# switching_noise_board.net
KiCad netlist of a schematic drawn in Altium Designer
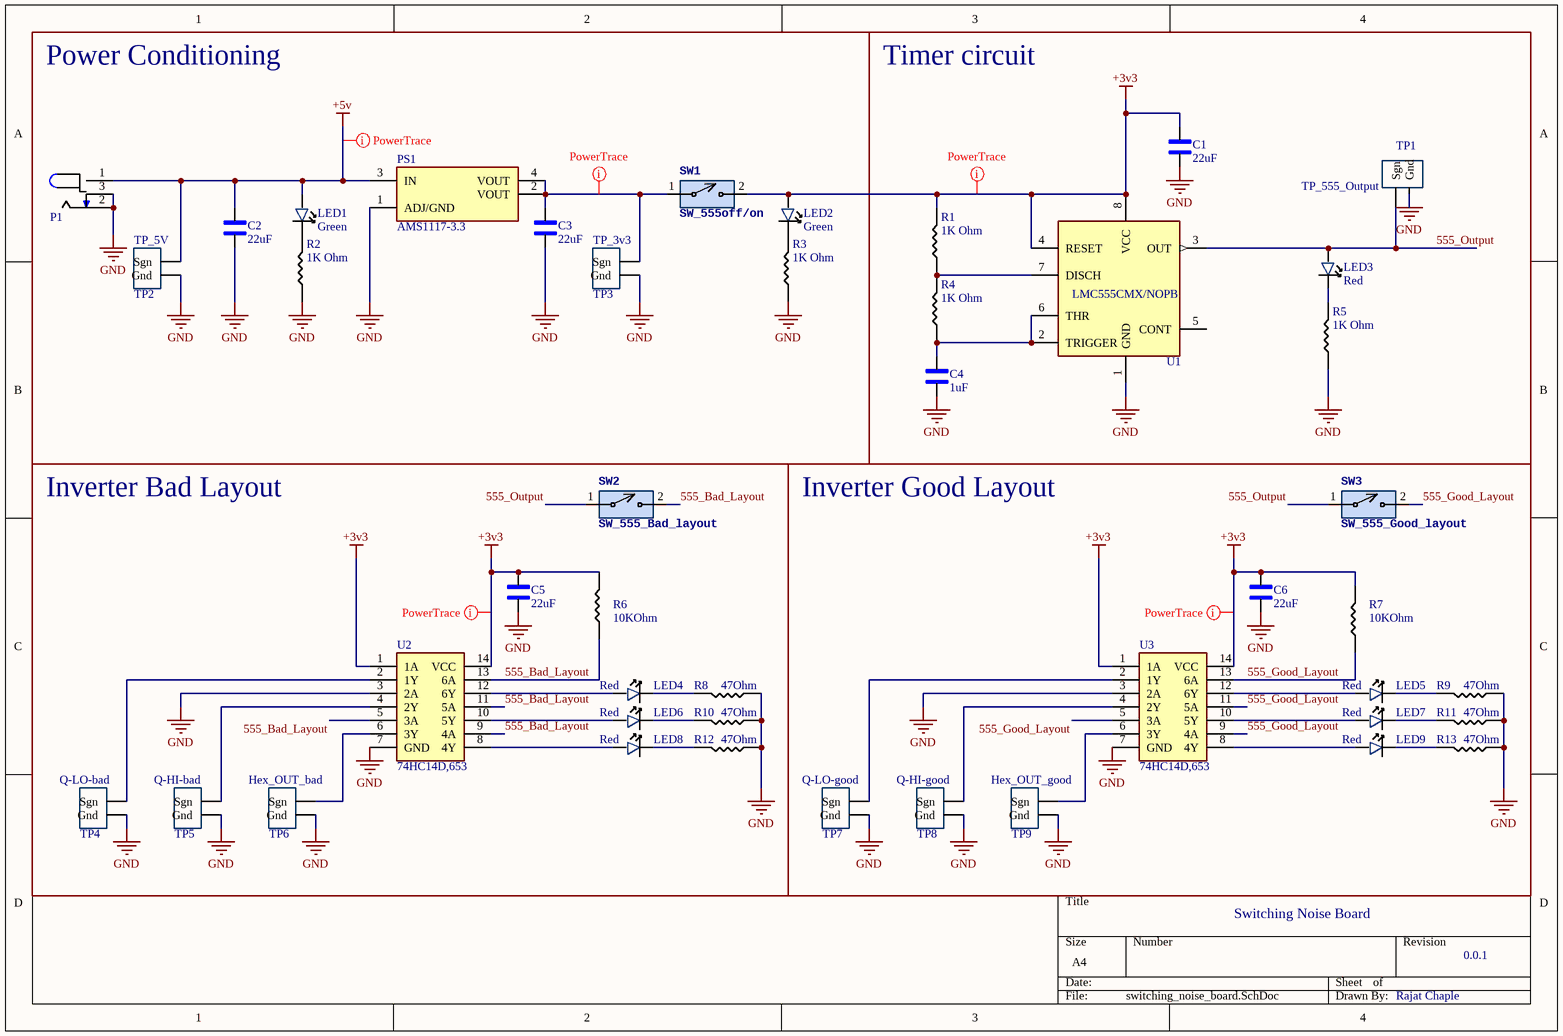
[diagram p0: switching_noise_board.SchDoc]

(export (version "E")
  (design (tool "Eeschema 10.0.6"))
  (components
    (comp (ref "C1")
      (value "22uF")
      (footprint "0805_Passive_Capaciitor")
      (description "MULTILAYER CERAMIC CAPACITORS MLCC - SMD/SMT 22UF 25V 0805 ROHS")
      (fields (field (name "MFR PART #") "CL21A226MAQNNNE") (field (name "LCSC PART#") "C45783"))
      (libsource (lib "ECEN5730Lib_JLC_2021_08") (part "C_22uF_0805"))
    )
    (comp (ref "C2")
      (value "22uF")
      (footprint "0805_Passive_Capaciitor")
      (description "MULTILAYER CERAMIC CAPACITORS MLCC - SMD/SMT 22UF 25V 0805 ROHS")
      (fields (field (name "MFR PART #") "CL21A226MAQNNNE") (field (name "LCSC PART#") "C45783"))
      (libsource (lib "ECEN5730Lib_JLC_2021_08") (part "C_22uF_0805"))
    )
    (comp (ref "C3")
      (value "22uF")
      (footprint "0805_Passive_Capaciitor")
      (description "MULTILAYER CERAMIC CAPACITORS MLCC - SMD/SMT 22UF 25V 0805 ROHS")
      (fields (field (name "MFR PART #") "CL21A226MAQNNNE") (field (name "LCSC PART#") "C45783"))
      (libsource (lib "ECEN5730Lib_JLC_2021_08") (part "C_22uF_0805"))
    )
    (comp (ref "C4")
      (value "1uF")
      (footprint "0402_Passive_Capacitor")
      (description "MULTILAYER CERAMIC CAPACITORS MLCC - SMD/SMT 1UF 25V 0402 ROHS")
      (fields (field (name "MFR PART #") "CL05A105KA5NQNC") (field (name "LCSC PART#") "C52923"))
      (libsource (lib "ECEN5730Lib_JLC_2021_08") (part "C_1uF_0402"))
    )
    (comp (ref "C5")
      (value "22uF")
      (footprint "0805_Passive_Capaciitor")
      (description "MULTILAYER CERAMIC CAPACITORS MLCC - SMD/SMT 22UF 25V 0805 ROHS")
      (fields (field (name "MFR PART #") "CL21A226MAQNNNE") (field (name "LCSC PART#") "C45783"))
      (libsource (lib "ECEN5730Lib_JLC_2021_08") (part "C_22uF_0805"))
    )
    (comp (ref "C6")
      (value "22uF")
      (footprint "0805_Passive_Capaciitor")
      (description "MULTILAYER CERAMIC CAPACITORS MLCC - SMD/SMT 22UF 25V 0805 ROHS")
      (fields (field (name "MFR PART #") "CL21A226MAQNNNE") (field (name "LCSC PART#") "C45783"))
      (libsource (lib "ECEN5730Lib_JLC_2021_08") (part "C_22uF_0805"))
    )
    (comp (ref "LED1")
      (value "Green")
      (footprint "LED_0603")
      (description "LIGHT EMITTING DIODES (LED) GREEN 520~535NM 112~258MCD@20MA TOP VIEW 0603 ROHS")
      (fields (field (name "MFR PART #") "19-217/GHC-YR1S2/3T") (field (name "LCSC PART#") "C72043"))
      (libsource (lib "ECEN5730Lib_JLC_2021_08") (part "LED_GREEN_0603"))
    )
    (comp (ref "LED2")
      (value "Green")
      (footprint "LED_0603")
      (description "LIGHT EMITTING DIODES (LED) GREEN 520~535NM 112~258MCD@20MA TOP VIEW 0603 ROHS")
      (fields (field (name "MFR PART #") "19-217/GHC-YR1S2/3T") (field (name "LCSC PART#") "C72043"))
      (libsource (lib "ECEN5730Lib_JLC_2021_08") (part "LED_GREEN_0603"))
    )
    (comp (ref "LED3")
      (value "Red")
      (footprint "LED_0603")
      (description "LIGHT EMITTING DIODES (LED) RED 520~625NM 90~100MCD@20MA TOP VIEW 0603 ROHS")
      (fields (field (name "MFR PART #") "KT-0603R") (field (name "LCSC PART#") "C2286"))
      (libsource (lib "ECEN5730Lib_JLC_2021_08") (part "LED_RED_0603"))
    )
    (comp (ref "LED4")
      (value "Red")
      (footprint "LED_0603")
      (description "LIGHT EMITTING DIODES (LED) RED 520~625NM 90~100MCD@20MA TOP VIEW 0603 ROHS")
      (fields (field (name "MFR PART #") "KT-0603R") (field (name "LCSC PART#") "C2286"))
      (libsource (lib "ECEN5730Lib_JLC_2021_08") (part "LED_RED_0603"))
    )
    (comp (ref "LED5")
      (value "Red")
      (footprint "LED_0603")
      (description "LIGHT EMITTING DIODES (LED) RED 520~625NM 90~100MCD@20MA TOP VIEW 0603 ROHS")
      (fields (field (name "MFR PART #") "KT-0603R") (field (name "LCSC PART#") "C2286"))
      (libsource (lib "ECEN5730Lib_JLC_2021_08") (part "LED_RED_0603"))
    )
    (comp (ref "LED6")
      (value "Red")
      (footprint "LED_0603")
      (description "LIGHT EMITTING DIODES (LED) RED 520~625NM 90~100MCD@20MA TOP VIEW 0603 ROHS")
      (fields (field (name "MFR PART #") "KT-0603R") (field (name "LCSC PART#") "C2286"))
      (libsource (lib "ECEN5730Lib_JLC_2021_08") (part "LED_RED_0603"))
    )
    (comp (ref "LED7")
      (value "Red")
      (footprint "LED_0603")
      (description "LIGHT EMITTING DIODES (LED) RED 520~625NM 90~100MCD@20MA TOP VIEW 0603 ROHS")
      (fields (field (name "MFR PART #") "KT-0603R") (field (name "LCSC PART#") "C2286"))
      (libsource (lib "ECEN5730Lib_JLC_2021_08") (part "LED_RED_0603"))
    )
    (comp (ref "LED8")
      (value "Red")
      (footprint "LED_0603")
      (description "LIGHT EMITTING DIODES (LED) RED 520~625NM 90~100MCD@20MA TOP VIEW 0603 ROHS")
      (fields (field (name "MFR PART #") "KT-0603R") (field (name "LCSC PART#") "C2286"))
      (libsource (lib "ECEN5730Lib_JLC_2021_08") (part "LED_RED_0603"))
    )
    (comp (ref "LED9")
      (value "Red")
      (footprint "LED_0603")
      (description "LIGHT EMITTING DIODES (LED) RED 520~625NM 90~100MCD@20MA TOP VIEW 0603 ROHS")
      (fields (field (name "MFR PART #") "KT-0603R") (field (name "LCSC PART#") "C2286"))
      (libsource (lib "ECEN5730Lib_JLC_2021_08") (part "LED_RED_0603"))
    )
    (comp (ref "P1")
      (value "Power Jack")
      (footprint "Power_Jack")
      (description "Power Barrel Connector Jack 2.10mm ID (0.083\"), 5.50mm OD (0.217\") Through Hole, Right Angle")
      (fields (field (name "DIGIKEY PART") "CP-102A-ND") (field (name "LCSC PART#") "C136744"))
      (libsource (lib "ECEN5730Lib_JLC_2021_08") (part "P_Power Jack"))
    )
    (comp (ref "PS1")
      (value "AMS1117-3.3")
      (footprint "LDO")
      (description "LOW DROPOUT REGULATORS(LDO) POSITIVE FIXED 1.3V @ 800MA 15V 3.3V 1A SOT-223 ROHS")
      (fields (field (name "LCSC PART#") "C6186"))
      (libsource (lib "ECEN5730Lib_JLC_2021_08") (part "PS_AMS_LDO_3v3"))
    )
    (comp (ref "R1")
      (value "1K Ohm")
      (footprint "0805_Passive_Resistor")
      (description "CHIP RESISTOR - SURFACE MOUNT 1KOHMS ±1% 1/8W 0805 ROHS")
      (fields (field (name "LCSC PART#") "C17513") (field (name "MFR PART #") "0805W8F1001T5E"))
      (libsource (lib "ECEN5730Lib_JLC_2021_08") (part "R_1K_0805"))
    )
    (comp (ref "R2")
      (value "1K Ohm")
      (footprint "0805_Passive_Resistor")
      (description "CHIP RESISTOR - SURFACE MOUNT 1KOHMS ±1% 1/8W 0805 ROHS")
      (fields (field (name "LCSC PART#") "C17513") (field (name "MFR PART #") "0805W8F1001T5E"))
      (libsource (lib "ECEN5730Lib_JLC_2021_08") (part "R_1K_0805"))
    )
    (comp (ref "R3")
      (value "1K Ohm")
      (footprint "0805_Passive_Resistor")
      (description "CHIP RESISTOR - SURFACE MOUNT 1KOHMS ±1% 1/8W 0805 ROHS")
      (fields (field (name "LCSC PART#") "C17513") (field (name "MFR PART #") "0805W8F1001T5E"))
      (libsource (lib "ECEN5730Lib_JLC_2021_08") (part "R_1K_0805"))
    )
    (comp (ref "R4")
      (value "1K Ohm")
      (footprint "0805_Passive_Resistor")
      (description "CHIP RESISTOR - SURFACE MOUNT 1KOHMS ±1% 1/8W 0805 ROHS")
      (fields (field (name "LCSC PART#") "C17513") (field (name "MFR PART #") "0805W8F1001T5E"))
      (libsource (lib "ECEN5730Lib_JLC_2021_08") (part "R_1K_0805"))
    )
    (comp (ref "R5")
      (value "1K Ohm")
      (footprint "0805_Passive_Resistor")
      (description "CHIP RESISTOR - SURFACE MOUNT 1KOHMS ±1% 1/8W 0805 ROHS")
      (fields (field (name "LCSC PART#") "C17513") (field (name "MFR PART #") "0805W8F1001T5E"))
      (libsource (lib "ECEN5730Lib_JLC_2021_08") (part "R_1K_0805"))
    )
    (comp (ref "R6")
      (value "10KOhm")
      (footprint "0402_Passive_Resistor")
      (description "CHIP RESISTOR - SURFACE MOUNT 10KOHMS ±1% 1/16W 0402 ROHS")
      (fields (field (name "MFR PART #") "0402WGF1002TCE") (field (name "LCSC PART#") "C25744"))
      (libsource (lib "ECEN5730Lib_JLC_2021_08") (part "R_10KOhm_0402"))
    )
    (comp (ref "R7")
      (value "10KOhm")
      (footprint "0402_Passive_Resistor")
      (description "CHIP RESISTOR - SURFACE MOUNT 10KOHMS ±1% 1/16W 0402 ROHS")
      (fields (field (name "MFR PART #") "0402WGF1002TCE") (field (name "LCSC PART#") "C25744"))
      (libsource (lib "ECEN5730Lib_JLC_2021_08") (part "R_10KOhm_0402"))
    )
    (comp (ref "R8")
      (value "47Ohm")
      (footprint "0402_Passive_Resistor")
      (description "CHIP RESISTOR - SURFACE MOUNT 47OHMS ±1% 1/16W 0402 ROHS")
      (fields (field (name "MFR PART #") "0402WGF470JTCE") (field (name "LCSC PART#") "C25118"))
      (libsource (lib "ECEN5730Lib_JLC_2021_08") (part "R_47Ohm_0402"))
    )
    (comp (ref "R9")
      (value "47Ohm")
      (footprint "0402_Passive_Resistor")
      (description "CHIP RESISTOR - SURFACE MOUNT 47OHMS ±1% 1/16W 0402 ROHS")
      (fields (field (name "MFR PART #") "0402WGF470JTCE") (field (name "LCSC PART#") "C25118"))
      (libsource (lib "ECEN5730Lib_JLC_2021_08") (part "R_47Ohm_0402"))
    )
    (comp (ref "R10")
      (value "47Ohm")
      (footprint "0402_Passive_Resistor")
      (description "CHIP RESISTOR - SURFACE MOUNT 47OHMS ±1% 1/16W 0402 ROHS")
      (fields (field (name "MFR PART #") "0402WGF470JTCE") (field (name "LCSC PART#") "C25118"))
      (libsource (lib "ECEN5730Lib_JLC_2021_08") (part "R_47Ohm_0402"))
    )
    (comp (ref "R11")
      (value "47Ohm")
      (footprint "0402_Passive_Resistor")
      (description "CHIP RESISTOR - SURFACE MOUNT 47OHMS ±1% 1/16W 0402 ROHS")
      (fields (field (name "MFR PART #") "0402WGF470JTCE") (field (name "LCSC PART#") "C25118"))
      (libsource (lib "ECEN5730Lib_JLC_2021_08") (part "R_47Ohm_0402"))
    )
    (comp (ref "R12")
      (value "47Ohm")
      (footprint "0402_Passive_Resistor")
      (description "CHIP RESISTOR - SURFACE MOUNT 47OHMS ±1% 1/16W 0402 ROHS")
      (fields (field (name "MFR PART #") "0402WGF470JTCE") (field (name "LCSC PART#") "C25118"))
      (libsource (lib "ECEN5730Lib_JLC_2021_08") (part "R_47Ohm_0402"))
    )
    (comp (ref "R13")
      (value "47Ohm")
      (footprint "0402_Passive_Resistor")
      (description "CHIP RESISTOR - SURFACE MOUNT 47OHMS ±1% 1/16W 0402 ROHS")
      (fields (field (name "MFR PART #") "0402WGF470JTCE") (field (name "LCSC PART#") "C25118"))
      (libsource (lib "ECEN5730Lib_JLC_2021_08") (part "R_47Ohm_0402"))
    )
    (comp (ref "SW1")
      (value "SW_555off/on")
      (footprint "2Pin-Header-Conn")
      (description "2Pin Header")
      (fields (field (name "LCSC PART#") "C124375"))
      (libsource (lib "ECEN5730Lib_JLC_2021_08") (part "SW_2Pin_100mil_Switch"))
    )
    (comp (ref "SW2")
      (value "SW_555_Bad_layout")
      (footprint "2Pin-Header-Conn")
      (description "2Pin Header")
      (fields (field (name "LCSC PART#") "C124375"))
      (libsource (lib "ECEN5730Lib_JLC_2021_08") (part "SW_2Pin_100mil_Switch"))
    )
    (comp (ref "SW3")
      (value "SW_555_Good_layout")
      (footprint "2Pin-Header-Conn")
      (description "2Pin Header")
      (fields (field (name "LCSC PART#") "C124375"))
      (libsource (lib "ECEN5730Lib_JLC_2021_08") (part "SW_2Pin_100mil_Switch"))
    )
    (comp (ref "TP1")
      (value "TP_555_Output")
      (footprint "TP10x_Probe")
      (description "Test Point 300 mil centers")
      (libsource (lib "") (part "TP_10x_Probe_1"))
    )
    (comp (ref "TP2")
      (value "TP_5V")
      (footprint "TP10x_Probe")
      (description "Test Point 300 mil centers")
      (libsource (lib "ECEN5730Lib_Manual_2021_08") (part "TP_10x_Probe"))
    )
    (comp (ref "TP3")
      (value "TP_3v3")
      (footprint "TP10x_Probe")
      (description "Test Point 300 mil centers")
      (libsource (lib "ECEN5730Lib_Manual_2021_08") (part "TP_10x_Probe"))
    )
    (comp (ref "TP4")
      (value "Q-LO-bad")
      (footprint "TP10x_Probe")
      (description "Test Point 300 mil centers")
      (libsource (lib "ECEN5730Lib_Manual_2021_08") (part "TP_10x_Probe"))
    )
    (comp (ref "TP5")
      (value "Q-HI-bad")
      (footprint "TP10x_Probe")
      (description "Test Point 300 mil centers")
      (libsource (lib "ECEN5730Lib_Manual_2021_08") (part "TP_10x_Probe"))
    )
    (comp (ref "TP6")
      (value "Hex_OUT_bad")
      (footprint "TP10x_Probe")
      (description "Test Point 300 mil centers")
      (libsource (lib "ECEN5730Lib_Manual_2021_08") (part "TP_10x_Probe"))
    )
    (comp (ref "TP7")
      (value "Q-LO-good")
      (footprint "TP10x_Probe")
      (description "Test Point 300 mil centers")
      (libsource (lib "ECEN5730Lib_Manual_2021_08") (part "TP_10x_Probe"))
    )
    (comp (ref "TP8")
      (value "Q-HI-good")
      (footprint "TP10x_Probe")
      (description "Test Point 300 mil centers")
      (libsource (lib "ECEN5730Lib_Manual_2021_08") (part "TP_10x_Probe"))
    )
    (comp (ref "TP9")
      (value "Hex_OUT_good")
      (footprint "TP10x_Probe")
      (description "Test Point 300 mil centers")
      (libsource (lib "ECEN5730Lib_Manual_2021_08") (part "TP_10x_Probe"))
    )
    (comp (ref "U1")
      (value "LMC555CMX/NOPB")
      (footprint "TS555IDTTR")
      (description "555 Type, Timer/Oscillator _Single_ IC 3MHz 8-SO")
      (fields (field (name "LCSC PART#") "C90760"))
      (libsource (lib "ECEN5730Lib_JLC_2021_08") (part "U_555_Fast"))
    )
    (comp (ref "U2")
      (value "74HC14D,653")
      (footprint "HEX_74AC14")
      (description "Inverter IC 6 Channel Schmitt Trigger 14-SOIC")
      (fields (field (name "LCSC PART#") "C5605"))
      (libsource (lib "ECEN5730Lib_JLC_2021_08") (part "U_7414_HC_Hex"))
    )
    (comp (ref "U3")
      (value "74HC14D,653")
      (footprint "HEX_74AC14")
      (description "Inverter IC 6 Channel Schmitt Trigger 14-SOIC")
      (fields (field (name "LCSC PART#") "C5605"))
      (libsource (lib "ECEN5730Lib_JLC_2021_08") (part "U_7414_HC_Hex"))
    )
  )
  (nets
    (net (code "1") (name "+3v3") (class "Default")
      (node (ref "C1") (pin "2") (pinfunction "2_2") (pintype "passive"))
      (node (ref "C5") (pin "2") (pinfunction "2_2") (pintype "passive"))
      (node (ref "C6") (pin "2") (pinfunction "2_2") (pintype "passive"))
      (node (ref "LED2") (pin "1") (pinfunction "1_1") (pintype "passive"))
      (node (ref "R1") (pin "2") (pinfunction "2_2") (pintype "passive"))
      (node (ref "R6") (pin "2") (pinfunction "2_2") (pintype "passive"))
      (node (ref "R7") (pin "2") (pinfunction "2_2") (pintype "passive"))
      (node (ref "SW1") (pin "2") (pinfunction "2_2") (pintype "passive"))
      (node (ref "U1") (pin "4") (pinfunction "RESET_4") (pintype "passive"))
      (node (ref "U1") (pin "8") (pinfunction "VCC_8") (pintype "power_in"))
      (node (ref "U2") (pin "1") (pinfunction "1A_1") (pintype "passive"))
      (node (ref "U2") (pin "14") (pinfunction "VCC_14") (pintype "passive"))
      (node (ref "U3") (pin "1") (pinfunction "1A_1") (pintype "passive"))
      (node (ref "U3") (pin "14") (pinfunction "VCC_14") (pintype "passive"))
    )
    (net (code "2") (name "+5v") (class "Default")
      (node (ref "C2") (pin "2") (pinfunction "2_2") (pintype "passive"))
      (node (ref "LED1") (pin "1") (pinfunction "1_1") (pintype "passive"))
      (node (ref "P1") (pin "1") (pinfunction "1_1") (pintype "power_in"))
      (node (ref "PS1") (pin "3") (pinfunction "IN_3") (pintype "power_in"))
      (node (ref "TP2") (pin "1") (pinfunction "Sgn_1") (pintype "passive"))
    )
    (net (code "3") (name "/555_Bad_Layout") (class "Default")
      (node (ref "R6") (pin "1") (pinfunction "1_1") (pintype "passive"))
      (node (ref "SW2") (pin "2") (pinfunction "2_2") (pintype "passive"))
      (node (ref "U2") (pin "11") (pinfunction "5A_11") (pintype "passive"))
      (node (ref "U2") (pin "13") (pinfunction "6A_13") (pintype "passive"))
      (node (ref "U2") (pin "5") (pinfunction "3A_5") (pintype "passive"))
      (node (ref "U2") (pin "9") (pinfunction "4A_9") (pintype "passive"))
    )
    (net (code "4") (name "/555_Good_Layout") (class "Default")
      (node (ref "R7") (pin "1") (pinfunction "1_1") (pintype "passive"))
      (node (ref "SW3") (pin "2") (pinfunction "2_2") (pintype "passive"))
      (node (ref "U3") (pin "11") (pinfunction "5A_11") (pintype "passive"))
      (node (ref "U3") (pin "13") (pinfunction "6A_13") (pintype "passive"))
      (node (ref "U3") (pin "5") (pinfunction "3A_5") (pintype "passive"))
      (node (ref "U3") (pin "9") (pinfunction "4A_9") (pintype "passive"))
    )
    (net (code "5") (name "/555_Output") (class "Default")
      (node (ref "LED3") (pin "1") (pinfunction "1_1") (pintype "passive"))
      (node (ref "SW2") (pin "1") (pinfunction "1_1") (pintype "passive"))
      (node (ref "SW3") (pin "1") (pinfunction "1_1") (pintype "passive"))
      (node (ref "TP1") (pin "1") (pinfunction "Sgn_1") (pintype "passive"))
      (node (ref "U1") (pin "3") (pinfunction "OUT_3") (pintype "output"))
    )
    (net (code "6") (name "GND") (class "Default")
      (node (ref "C1") (pin "1") (pinfunction "1_1") (pintype "passive"))
      (node (ref "C2") (pin "1") (pinfunction "1_1") (pintype "passive"))
      (node (ref "C3") (pin "1") (pinfunction "1_1") (pintype "passive"))
      (node (ref "C4") (pin "1") (pinfunction "1_1") (pintype "passive"))
      (node (ref "C5") (pin "1") (pinfunction "1_1") (pintype "passive"))
      (node (ref "C6") (pin "1") (pinfunction "1_1") (pintype "passive"))
      (node (ref "P1") (pin "2") (pinfunction "2_2") (pintype "power_in"))
      (node (ref "P1") (pin "3") (pinfunction "3_3") (pintype "power_in"))
      (node (ref "PS1") (pin "1") (pinfunction "ADJ/GND_1") (pintype "passive"))
      (node (ref "R10") (pin "1") (pinfunction "1_1") (pintype "passive"))
      (node (ref "R11") (pin "1") (pinfunction "1_1") (pintype "passive"))
      (node (ref "R12") (pin "1") (pinfunction "1_1") (pintype "passive"))
      (node (ref "R13") (pin "1") (pinfunction "1_1") (pintype "passive"))
      (node (ref "R2") (pin "1") (pinfunction "1_1") (pintype "passive"))
      (node (ref "R3") (pin "1") (pinfunction "1_1") (pintype "passive"))
      (node (ref "R5") (pin "1") (pinfunction "1_1") (pintype "passive"))
      (node (ref "R8") (pin "1") (pinfunction "1_1") (pintype "passive"))
      (node (ref "R9") (pin "1") (pinfunction "1_1") (pintype "passive"))
      (node (ref "TP1") (pin "2") (pinfunction "Gnd_2") (pintype "passive"))
      (node (ref "TP2") (pin "2") (pinfunction "Gnd_2") (pintype "passive"))
      (node (ref "TP3") (pin "2") (pinfunction "Gnd_2") (pintype "passive"))
      (node (ref "TP4") (pin "2") (pinfunction "Gnd_2") (pintype "passive"))
      (node (ref "TP5") (pin "2") (pinfunction "Gnd_2") (pintype "passive"))
      (node (ref "TP6") (pin "2") (pinfunction "Gnd_2") (pintype "passive"))
      (node (ref "TP7") (pin "2") (pinfunction "Gnd_2") (pintype "passive"))
      (node (ref "TP8") (pin "2") (pinfunction "Gnd_2") (pintype "passive"))
      (node (ref "TP9") (pin "2") (pinfunction "Gnd_2") (pintype "passive"))
      (node (ref "U1") (pin "1") (pinfunction "GND_1") (pintype "power_in"))
      (node (ref "U2") (pin "3") (pinfunction "2A_3") (pintype "passive"))
      (node (ref "U2") (pin "7") (pinfunction "GND_7") (pintype "passive"))
      (node (ref "U3") (pin "3") (pinfunction "2A_3") (pintype "passive"))
      (node (ref "U3") (pin "7") (pinfunction "GND_7") (pintype "passive"))
    )
    (net (code "7") (name "Net-(LED1-Pad2)") (class "Default")
      (node (ref "LED1") (pin "2") (pinfunction "2_2") (pintype "passive"))
      (node (ref "R2") (pin "2") (pinfunction "2_2") (pintype "passive"))
    )
    (net (code "8") (name "Net-(LED2-Pad2)") (class "Default")
      (node (ref "LED2") (pin "2") (pinfunction "2_2") (pintype "passive"))
      (node (ref "R3") (pin "2") (pinfunction "2_2") (pintype "passive"))
    )
    (net (code "9") (name "Net-(LED3-Pad2)") (class "Default")
      (node (ref "LED3") (pin "2") (pinfunction "2_2") (pintype "passive"))
      (node (ref "R5") (pin "2") (pinfunction "2_2") (pintype "passive"))
    )
    (net (code "10") (name "Net-(LED4-Pad2)") (class "Default")
      (node (ref "LED4") (pin "2") (pinfunction "2_2") (pintype "passive"))
      (node (ref "R8") (pin "2") (pinfunction "2_2") (pintype "passive"))
    )
    (net (code "11") (name "Net-(LED5-Pad2)") (class "Default")
      (node (ref "LED5") (pin "2") (pinfunction "2_2") (pintype "passive"))
      (node (ref "R9") (pin "2") (pinfunction "2_2") (pintype "passive"))
    )
    (net (code "12") (name "Net-(LED6-Pad2)") (class "Default")
      (node (ref "LED6") (pin "2") (pinfunction "2_2") (pintype "passive"))
      (node (ref "R10") (pin "2") (pinfunction "2_2") (pintype "passive"))
    )
    (net (code "13") (name "Net-(LED7-Pad2)") (class "Default")
      (node (ref "LED7") (pin "2") (pinfunction "2_2") (pintype "passive"))
      (node (ref "R11") (pin "2") (pinfunction "2_2") (pintype "passive"))
    )
    (net (code "14") (name "Net-(LED8-Pad2)") (class "Default")
      (node (ref "LED8") (pin "2") (pinfunction "2_2") (pintype "passive"))
      (node (ref "R12") (pin "2") (pinfunction "2_2") (pintype "passive"))
    )
    (net (code "15") (name "Net-(LED9-Pad2)") (class "Default")
      (node (ref "LED9") (pin "2") (pinfunction "2_2") (pintype "passive"))
      (node (ref "R13") (pin "2") (pinfunction "2_2") (pintype "passive"))
    )
    (net (code "16") (name "Net-(TP3-Sgn)") (class "Default")
      (node (ref "C3") (pin "2") (pinfunction "2_2") (pintype "passive"))
      (node (ref "PS1") (pin "2") (pinfunction "VOUT_2") (pintype "power_in"))
      (node (ref "PS1") (pin "4") (pinfunction "VOUT_4") (pintype "power_in"))
      (node (ref "SW1") (pin "1") (pinfunction "1_1") (pintype "passive"))
      (node (ref "TP3") (pin "1") (pinfunction "Sgn_1") (pintype "passive"))
    )
    (net (code "17") (name "Net-(TP4-Sgn)") (class "Default")
      (node (ref "TP4") (pin "1") (pinfunction "Sgn_1") (pintype "passive"))
      (node (ref "U2") (pin "2") (pinfunction "1Y_2") (pintype "passive"))
    )
    (net (code "18") (name "Net-(TP5-Sgn)") (class "Default")
      (node (ref "TP5") (pin "1") (pinfunction "Sgn_1") (pintype "passive"))
      (node (ref "U2") (pin "4") (pinfunction "2Y_4") (pintype "passive"))
    )
    (net (code "19") (name "Net-(TP6-Sgn)") (class "Default")
      (node (ref "TP6") (pin "1") (pinfunction "Sgn_1") (pintype "passive"))
      (node (ref "U2") (pin "6") (pinfunction "3Y_6") (pintype "passive"))
    )
    (net (code "20") (name "Net-(TP7-Sgn)") (class "Default")
      (node (ref "TP7") (pin "1") (pinfunction "Sgn_1") (pintype "passive"))
      (node (ref "U3") (pin "2") (pinfunction "1Y_2") (pintype "passive"))
    )
    (net (code "21") (name "Net-(TP8-Sgn)") (class "Default")
      (node (ref "TP8") (pin "1") (pinfunction "Sgn_1") (pintype "passive"))
      (node (ref "U3") (pin "4") (pinfunction "2Y_4") (pintype "passive"))
    )
    (net (code "22") (name "Net-(TP9-Sgn)") (class "Default")
      (node (ref "TP9") (pin "1") (pinfunction "Sgn_1") (pintype "passive"))
      (node (ref "U3") (pin "6") (pinfunction "3Y_6") (pintype "passive"))
    )
    (net (code "23") (name "Net-(U1-DISCH)") (class "Default")
      (node (ref "R1") (pin "1") (pinfunction "1_1") (pintype "passive"))
      (node (ref "R4") (pin "2") (pinfunction "2_2") (pintype "passive"))
      (node (ref "U1") (pin "7") (pinfunction "DISCH_7") (pintype "passive"))
    )
    (net (code "24") (name "Net-(U1-THR)") (class "Default")
      (node (ref "C4") (pin "2") (pinfunction "2_2") (pintype "passive"))
      (node (ref "R4") (pin "1") (pinfunction "1_1") (pintype "passive"))
      (node (ref "U1") (pin "2") (pinfunction "TRIGGER_2") (pintype "passive"))
      (node (ref "U1") (pin "6") (pinfunction "THR_6") (pintype "passive"))
    )
    (net (code "25") (name "Net-(U2-4Y)") (class "Default")
      (node (ref "LED8") (pin "1") (pinfunction "1_1") (pintype "passive"))
      (node (ref "U2") (pin "8") (pinfunction "4Y_8") (pintype "passive"))
    )
    (net (code "26") (name "Net-(U2-5Y)") (class "Default")
      (node (ref "LED6") (pin "1") (pinfunction "1_1") (pintype "passive"))
      (node (ref "U2") (pin "10") (pinfunction "5Y_10") (pintype "passive"))
    )
    (net (code "27") (name "Net-(U2-6Y)") (class "Default")
      (node (ref "LED4") (pin "1") (pinfunction "1_1") (pintype "passive"))
      (node (ref "U2") (pin "12") (pinfunction "6Y_12") (pintype "passive"))
    )
    (net (code "28") (name "Net-(U3-4Y)") (class "Default")
      (node (ref "LED9") (pin "1") (pinfunction "1_1") (pintype "passive"))
      (node (ref "U3") (pin "8") (pinfunction "4Y_8") (pintype "passive"))
    )
    (net (code "29") (name "Net-(U3-5Y)") (class "Default")
      (node (ref "LED7") (pin "1") (pinfunction "1_1") (pintype "passive"))
      (node (ref "U3") (pin "10") (pinfunction "5Y_10") (pintype "passive"))
    )
    (net (code "30") (name "Net-(U3-6Y)") (class "Default")
      (node (ref "LED5") (pin "1") (pinfunction "1_1") (pintype "passive"))
      (node (ref "U3") (pin "12") (pinfunction "6Y_12") (pintype "passive"))
    )
    (net (code "31") (name "unconnected-(U1-CONT-Pad5)") (class "Default")
      (node (ref "U1") (pin "5") (pinfunction "CONT_5") (pintype "passive"))
    )
  )
)
